# circuit.net
KiCad netlist of a schematic drawn in EAGLE
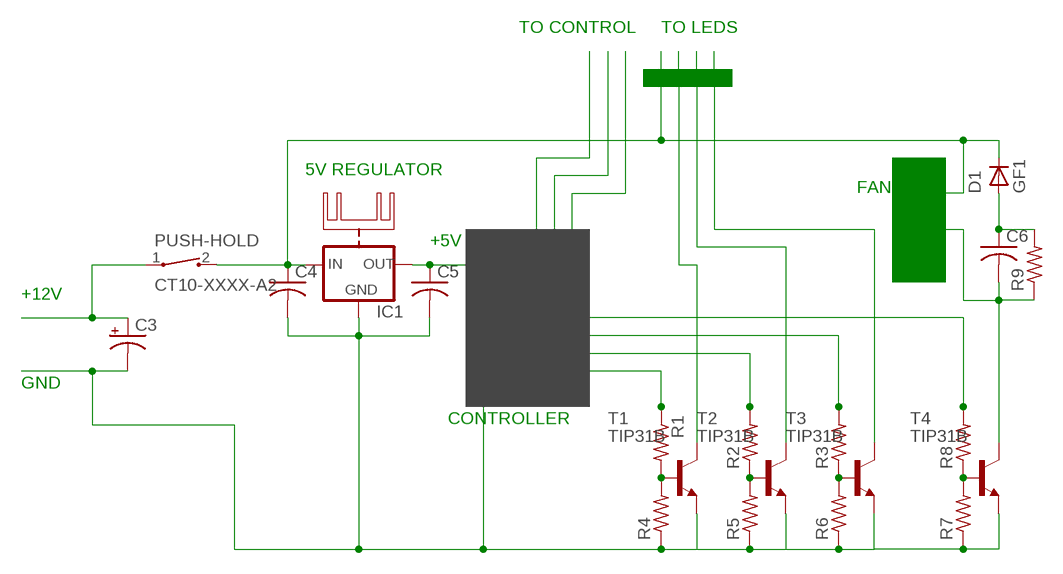
[diagram p0: schematic, sheet 1]

(export (version "E")
  (design (tool "Eeschema 10.0.6"))
  (components
    (comp (ref "C3")
      (value "CPOL-US150CLZ-0810")
      (footprint "eagle-import:150CLZ-0810")
      (libsource (lib "eagle-import") (part "CPOL-US150CLZ-0810"))
    )
    (comp (ref "C4")
      (value "C-USC1812")
      (footprint "eagle-import:C1812")
      (libsource (lib "eagle-import") (part "C-USC1812"))
    )
    (comp (ref "C5")
      (value "C-USC1812")
      (footprint "eagle-import:C1812")
      (libsource (lib "eagle-import") (part "C-USC1812"))
    )
    (comp (ref "C6")
      (value "C-USC1812")
      (footprint "eagle-import:C1812")
      (libsource (lib "eagle-import") (part "C-USC1812"))
    )
    (comp (ref "D1")
      (value "GF1")
      (footprint "eagle-import:SMA-DO214AC")
      (libsource (lib "eagle-import") (part "GF1"))
    )
    (comp (ref "IC1")
      (value "78XXH")
      (footprint "eagle-import:78XXH")
      (libsource (lib "eagle-import") (part "78XXH"))
    )
    (comp (ref "PUSH-HOLD")
      (value "CT10-XXXX-A2")
      (footprint "eagle-import:CT10-XXXX-A2")
      (libsource (lib "eagle-import") (part "CT10-XXXX-A2"))
    )
    (comp (ref "R1")
      (value "R-US_0207/10")
      (footprint "eagle-import:0207_10")
      (libsource (lib "eagle-import") (part "R-US_0207/10"))
    )
    (comp (ref "R2")
      (value "R-US_0207/10")
      (footprint "eagle-import:0207_10")
      (libsource (lib "eagle-import") (part "R-US_0207/10"))
    )
    (comp (ref "R3")
      (value "R-US_0207/10")
      (footprint "eagle-import:0207_10")
      (libsource (lib "eagle-import") (part "R-US_0207/10"))
    )
    (comp (ref "R4")
      (value "R-US_0207/10")
      (footprint "eagle-import:0207_10")
      (libsource (lib "eagle-import") (part "R-US_0207/10"))
    )
    (comp (ref "R5")
      (value "R-US_0207/10")
      (footprint "eagle-import:0207_10")
      (libsource (lib "eagle-import") (part "R-US_0207/10"))
    )
    (comp (ref "R6")
      (value "R-US_0207/10")
      (footprint "eagle-import:0207_10")
      (libsource (lib "eagle-import") (part "R-US_0207/10"))
    )
    (comp (ref "R7")
      (value "R-US_0207/12")
      (footprint "eagle-import:0207_12")
      (libsource (lib "eagle-import") (part "R-US_0207/12"))
    )
    (comp (ref "R8")
      (value "R-US_0207/12")
      (footprint "eagle-import:0207_12")
      (libsource (lib "eagle-import") (part "R-US_0207/12"))
    )
    (comp (ref "R9")
      (value "R-US_0309/10")
      (footprint "eagle-import:0309_10")
      (libsource (lib "eagle-import") (part "R-US_0309/10"))
    )
    (comp (ref "T1")
      (value "TIP31B")
      (footprint "eagle-import:TO220")
      (libsource (lib "eagle-import") (part "TIP31B"))
    )
    (comp (ref "T2")
      (value "TIP31B")
      (footprint "eagle-import:TO220")
      (libsource (lib "eagle-import") (part "TIP31B"))
    )
    (comp (ref "T3")
      (value "TIP31B")
      (footprint "eagle-import:TO220")
      (libsource (lib "eagle-import") (part "TIP31B"))
    )
    (comp (ref "T4")
      (value "TIP31B")
      (footprint "eagle-import:TO220")
      (libsource (lib "eagle-import") (part "TIP31B"))
    )
  )
  (nets
    (net (code "1") (name "Net-(C3-Pad+)") (class "Default")
      (node (ref "C3") (pin "+") (pinfunction "+_+") (pintype "passive"))
      (node (ref "PUSH-HOLD") (pin "1") (pinfunction "1_1") (pintype "passive"))
    )
    (net (code "2") (name "Net-(C5-Pad1)") (class "Default")
      (node (ref "C5") (pin "1") (pinfunction "1_1") (pintype "passive"))
      (node (ref "IC1") (pin "OUT") (pinfunction "OUT_OUT") (pintype "passive"))
    )
    (net (code "3") (name "Net-(C6-Pad1)") (class "Default")
      (node (ref "C6") (pin "1") (pinfunction "1_1") (pintype "passive"))
      (node (ref "D1") (pin "A") (pinfunction "A_A") (pintype "passive"))
      (node (ref "R9") (pin "2") (pinfunction "2_2") (pintype "passive"))
    )
    (net (code "4") (name "Net-(D1-C)") (class "Default")
      (node (ref "C4") (pin "1") (pinfunction "1_1") (pintype "passive"))
      (node (ref "D1") (pin "K") (pinfunction "C_K") (pintype "passive"))
      (node (ref "IC1") (pin "IN") (pinfunction "IN_IN") (pintype "input"))
      (node (ref "PUSH-HOLD") (pin "2") (pinfunction "2_2") (pintype "passive"))
    )
    (net (code "5") (name "Net-(T1-B)") (class "Default")
      (node (ref "R1") (pin "2") (pinfunction "2_2") (pintype "passive"))
      (node (ref "R4") (pin "2") (pinfunction "2_2") (pintype "passive"))
      (node (ref "T1") (pin "1") (pinfunction "B_1") (pintype "passive"))
    )
    (net (code "6") (name "Net-(T1-E)") (class "Default")
      (node (ref "C3") (pin "-") (pinfunction "-_-") (pintype "passive"))
      (node (ref "C4") (pin "2") (pinfunction "2_2") (pintype "passive"))
      (node (ref "C5") (pin "2") (pinfunction "2_2") (pintype "passive"))
      (node (ref "IC1") (pin "GND") (pinfunction "GND_GND") (pintype "input"))
      (node (ref "R4") (pin "1") (pinfunction "1_1") (pintype "passive"))
      (node (ref "R5") (pin "1") (pinfunction "1_1") (pintype "passive"))
      (node (ref "R6") (pin "1") (pinfunction "1_1") (pintype "passive"))
      (node (ref "R7") (pin "1") (pinfunction "1_1") (pintype "passive"))
      (node (ref "T1") (pin "3") (pinfunction "E_3") (pintype "passive"))
      (node (ref "T2") (pin "3") (pinfunction "E_3") (pintype "passive"))
      (node (ref "T3") (pin "3") (pinfunction "E_3") (pintype "passive"))
      (node (ref "T4") (pin "3") (pinfunction "E_3") (pintype "passive"))
    )
    (net (code "7") (name "Net-(T2-B)") (class "Default")
      (node (ref "R2") (pin "1") (pinfunction "1_1") (pintype "passive"))
      (node (ref "R5") (pin "2") (pinfunction "2_2") (pintype "passive"))
      (node (ref "T2") (pin "1") (pinfunction "B_1") (pintype "passive"))
    )
    (net (code "8") (name "Net-(T3-B)") (class "Default")
      (node (ref "R3") (pin "1") (pinfunction "1_1") (pintype "passive"))
      (node (ref "R6") (pin "2") (pinfunction "2_2") (pintype "passive"))
      (node (ref "T3") (pin "1") (pinfunction "B_1") (pintype "passive"))
    )
    (net (code "9") (name "Net-(T4-B)") (class "Default")
      (node (ref "R7") (pin "2") (pinfunction "2_2") (pintype "passive"))
      (node (ref "R8") (pin "1") (pinfunction "1_1") (pintype "passive"))
      (node (ref "T4") (pin "1") (pinfunction "B_1") (pintype "passive"))
    )
    (net (code "10") (name "Net-(T4-C)") (class "Default")
      (node (ref "C6") (pin "2") (pinfunction "2_2") (pintype "passive"))
      (node (ref "R9") (pin "1") (pinfunction "1_1") (pintype "passive"))
      (node (ref "T4") (pin "2") (pinfunction "C_2") (pintype "passive"))
    )
    (net (code "11") (name "unconnected-(R1-Pad1)") (class "Default")
      (node (ref "R1") (pin "1") (pinfunction "1_1") (pintype "passive"))
    )
    (net (code "12") (name "unconnected-(R2-Pad2)") (class "Default")
      (node (ref "R2") (pin "2") (pinfunction "2_2") (pintype "passive"))
    )
    (net (code "13") (name "unconnected-(R3-Pad2)") (class "Default")
      (node (ref "R3") (pin "2") (pinfunction "2_2") (pintype "passive"))
    )
    (net (code "14") (name "unconnected-(R8-Pad2)") (class "Default")
      (node (ref "R8") (pin "2") (pinfunction "2_2") (pintype "passive"))
    )
    (net (code "15") (name "unconnected-(T1-C-Pad2)") (class "Default")
      (node (ref "T1") (pin "2") (pinfunction "C_2") (pintype "passive"))
    )
    (net (code "16") (name "unconnected-(T2-C-Pad2)") (class "Default")
      (node (ref "T2") (pin "2") (pinfunction "C_2") (pintype "passive"))
    )
    (net (code "17") (name "unconnected-(T3-C-Pad2)") (class "Default")
      (node (ref "T3") (pin "2") (pinfunction "C_2") (pintype "passive"))
    )
  )
)
